# LamplightController.net
KiCad netlist of a schematic drawn in Altium Designer
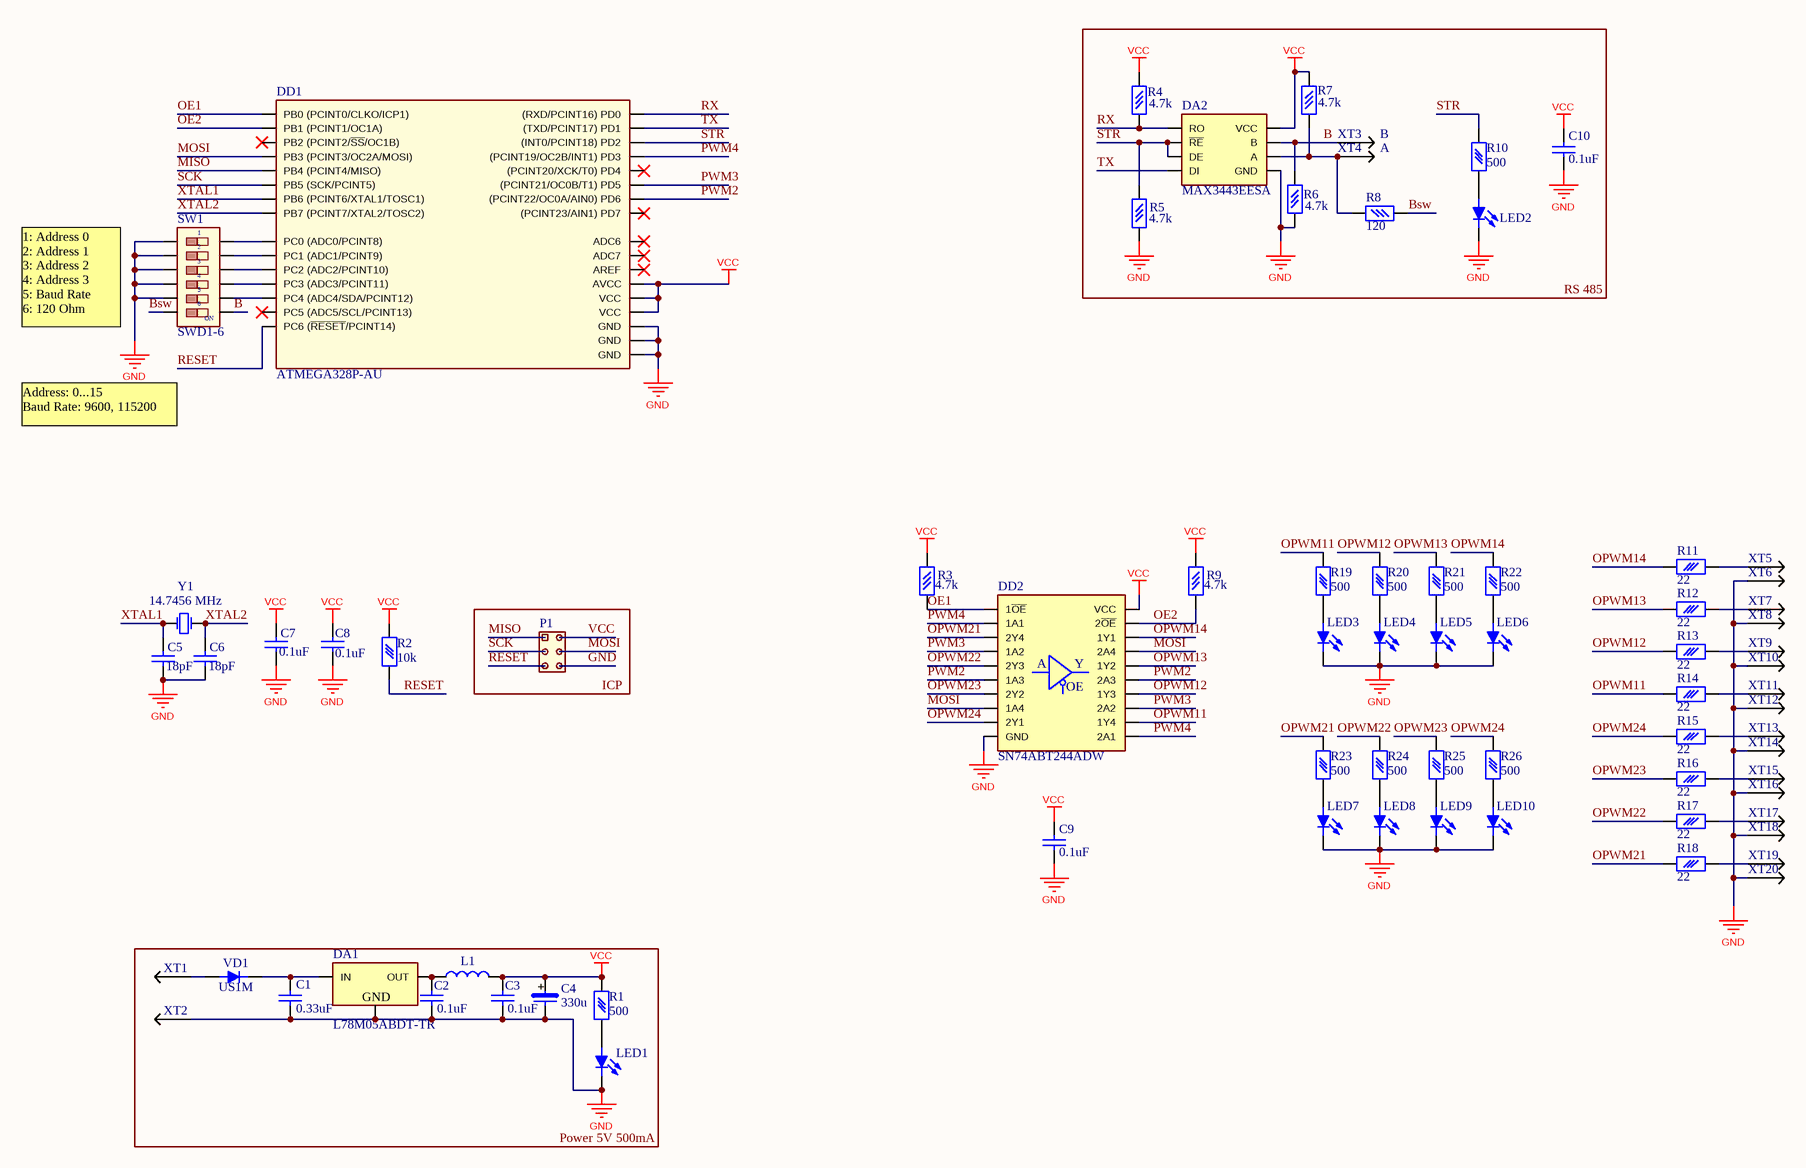
[diagram p0: LamplightController.SchDoc]

(export (version "E")
  (design (tool "Eeschema 10.0.6"))
  (components
    (comp (ref "C1")
      (value "0.33uF")
      (footprint "1206_CAP")
      (description "Конденсатор (1206)")
      (fields (field (name "Comment") "C_1206"))
      (libsource (lib "ElF_Lib") (part "C_1206"))
    )
    (comp (ref "C2")
      (value "0.1uF")
      (footprint "0603_CAP")
      (description "Конденсатор (0603)")
      (fields (field (name "Comment") "C_0603"))
      (libsource (lib "ElF_Lib") (part "C_0603"))
    )
    (comp (ref "C3")
      (value "0.1uF")
      (footprint "0603_CAP")
      (description "Конденсатор (0603)")
      (fields (field (name "Comment") "C_0603"))
      (libsource (lib "ElF_Lib") (part "C_0603"))
    )
    (comp (ref "C4")
      (value "330u")
      (footprint "case D")
      (description "Танаталовый чип конденсатор (Case D)")
      (fields (field (name "Comment") "C_caseD"))
      (libsource (lib "ElF_Lib") (part "C_caseD"))
    )
    (comp (ref "C5")
      (value "18pF")
      (footprint "0603_CAP")
      (description "Конденсатор (0603)")
      (fields (field (name "Comment") "C_0603"))
      (libsource (lib "ElF_Lib") (part "C_0603"))
    )
    (comp (ref "C6")
      (value "18pF")
      (footprint "0603_CAP")
      (description "Конденсатор (0603)")
      (fields (field (name "Comment") "C_0603"))
      (libsource (lib "ElF_Lib") (part "C_0603"))
    )
    (comp (ref "C7")
      (value "0.1uF")
      (footprint "0603_CAP")
      (description "Конденсатор (0603)")
      (fields (field (name "Comment") "C_0603"))
      (libsource (lib "ElF_Lib") (part "C_0603"))
    )
    (comp (ref "C8")
      (value "0.1uF")
      (footprint "0603_CAP")
      (description "Конденсатор (0603)")
      (fields (field (name "Comment") "C_0603"))
      (libsource (lib "ElF_Lib") (part "C_0603"))
    )
    (comp (ref "C9")
      (value "0.1uF")
      (footprint "0603_CAP")
      (description "Конденсатор (0603)")
      (fields (field (name "Comment") "C_0603"))
      (libsource (lib "ElF_Lib") (part "C_0603"))
    )
    (comp (ref "C10")
      (value "0.1uF")
      (footprint "0603_CAP")
      (description "Конденсатор (0603)")
      (fields (field (name "Comment") "C_0603"))
      (libsource (lib "ElF_Lib") (part "C_0603"))
    )
    (comp (ref "DA1")
      (value "L78M05ABDT-TR")
      (footprint "DPACK")
      (description "Precision 500 mA regulator 5V")
      (libsource (lib "ElF_Lib") (part "L78M05ABDT-TR"))
    )
    (comp (ref "DA2")
      (value "MAX3443EESA")
      (footprint "SOIC8")
      (description "5 V RS-485 Transceiver")
      (fields
        (field (name "MANUFACTURER") "Maxim Integrated Products")
        (field (name "MANUFACTURER PART NUMBER") "MAX3443EESA+")
      )
      (libsource (lib "ElF_Lib") (part "MAX3443EESA"))
    )
    (comp (ref "DD1")
      (value "ATMEGA328P-AU")
      (footprint "TQFP32")
      (description "ATMEL 8-BIT MICROCONTROLLER WITH 32KBYTES  IN-SYSTEM PROGRAMMABLE FLASH 2K RAM 20MHz")
      (libsource (lib "ElF_Lib") (part "ATMEGA328P-AU"))
    )
    (comp (ref "DD2")
      (value "SN74ABT244ADW")
      (footprint "SOIC20")
      (description "Octal Buffers/Drivers with 3-state outputs")
      (libsource (lib "ElF_Lib") (part "SN74ABT244ADW"))
    )
    (comp (ref "L1")
      (value "BLM21")
      (footprint "0805_IND")
      (description "Chip Ferrite Bead (0805 Size) BLM21PG221SH1")
      (libsource (lib "ElF_Lib") (part "BLM21"))
    )
    (comp (ref "LED1")
      (value "LED_0603")
      (footprint "0603_LED")
      (description "Светодиод 0603")
      (libsource (lib "ElF_Lib") (part "LED_0603"))
    )
    (comp (ref "LED2")
      (value "LED_0603")
      (footprint "0603_LED")
      (description "Светодиод 0603")
      (libsource (lib "ElF_Lib") (part "LED_0603"))
    )
    (comp (ref "LED3")
      (value "LED_0603")
      (footprint "0603_LED")
      (description "Светодиод 0603")
      (libsource (lib "ElF_Lib") (part "LED_0603"))
    )
    (comp (ref "LED4")
      (value "LED_0603")
      (footprint "0603_LED")
      (description "Светодиод 0603")
      (libsource (lib "ElF_Lib") (part "LED_0603"))
    )
    (comp (ref "LED5")
      (value "LED_0603")
      (footprint "0603_LED")
      (description "Светодиод 0603")
      (libsource (lib "ElF_Lib") (part "LED_0603"))
    )
    (comp (ref "LED6")
      (value "LED_0603")
      (footprint "0603_LED")
      (description "Светодиод 0603")
      (libsource (lib "ElF_Lib") (part "LED_0603"))
    )
    (comp (ref "LED7")
      (value "LED_0603")
      (footprint "0603_LED")
      (description "Светодиод 0603")
      (libsource (lib "ElF_Lib") (part "LED_0603"))
    )
    (comp (ref "LED8")
      (value "LED_0603")
      (footprint "0603_LED")
      (description "Светодиод 0603")
      (libsource (lib "ElF_Lib") (part "LED_0603"))
    )
    (comp (ref "LED9")
      (value "LED_0603")
      (footprint "0603_LED")
      (description "Светодиод 0603")
      (libsource (lib "ElF_Lib") (part "LED_0603"))
    )
    (comp (ref "LED10")
      (value "LED_0603")
      (footprint "0603_LED")
      (description "Светодиод 0603")
      (libsource (lib "ElF_Lib") (part "LED_0603"))
    )
    (comp (ref "P1") (value "BH-06M") (footprint "BH-06M") (libsource (lib "ElF_Lib") (part "BH-06M")))
    (comp (ref "R1")
      (value "500")
      (footprint "0603_RES")
      (description "Резистор 0.1 Вт (0603)")
      (fields (field (name "Comment") "R_0603"))
      (libsource (lib "") (part "R_0603_3"))
    )
    (comp (ref "R2")
      (value "10k")
      (footprint "0603_RES")
      (description "Резистор 0.1 Вт (0603)")
      (fields (field (name "Comment") "R_0603"))
      (libsource (lib "") (part "R_0603_3"))
    )
    (comp (ref "R3")
      (value "4.7k")
      (footprint "0603_RES")
      (description "Резистор 0.063 Вт (0603)")
      (fields (field (name "Comment") "R_0603"))
      (libsource (lib "") (part "R_0603_2"))
    )
    (comp (ref "R4")
      (value "4.7k")
      (footprint "0603_RES")
      (description "Резистор 0.063 Вт (0603)")
      (fields (field (name "Comment") "R_0603"))
      (libsource (lib "") (part "R_0603_2"))
    )
    (comp (ref "R5")
      (value "4.7k")
      (footprint "0603_RES")
      (description "Резистор 0.063 Вт (0603)")
      (fields (field (name "Comment") "R_0603"))
      (libsource (lib "") (part "R_0603_2"))
    )
    (comp (ref "R6")
      (value "4.7k")
      (footprint "0603_RES")
      (description "Резистор 0.063 Вт (0603)")
      (fields (field (name "Comment") "R_0603"))
      (libsource (lib "") (part "R_0603_2"))
    )
    (comp (ref "R7")
      (value "4.7k")
      (footprint "0603_RES")
      (description "Резистор 0.063 Вт (0603)")
      (fields (field (name "Comment") "R_0603"))
      (libsource (lib "") (part "R_0603_2"))
    )
    (comp (ref "R8")
      (value "120")
      (footprint "0603_RES")
      (description "Резистор 0.063 Вт (0603)")
      (fields (field (name "Comment") "R_0603"))
      (libsource (lib "") (part "R_0603_4"))
    )
    (comp (ref "R9")
      (value "4.7k")
      (footprint "0603_RES")
      (description "Резистор 0.063 Вт (0603)")
      (fields (field (name "Comment") "R_0603"))
      (libsource (lib "") (part "R_0603_2"))
    )
    (comp (ref "R10")
      (value "500")
      (footprint "0603_RES")
      (description "Резистор 0.1 Вт (0603)")
      (fields (field (name "Comment") "R_0603"))
      (libsource (lib "") (part "R_0603_3"))
    )
    (comp (ref "R11")
      (value "22")
      (footprint "0603_RES")
      (description "Резистор 0.1 Вт (0603)")
      (fields (field (name "Comment") "R_0603"))
      (libsource (lib "ElF_Lib") (part "R_0603"))
    )
    (comp (ref "R12")
      (value "22")
      (footprint "0603_RES")
      (description "Резистор 0.1 Вт (0603)")
      (fields (field (name "Comment") "R_0603"))
      (libsource (lib "ElF_Lib") (part "R_0603"))
    )
    (comp (ref "R13")
      (value "22")
      (footprint "0603_RES")
      (description "Резистор 0.1 Вт (0603)")
      (fields (field (name "Comment") "R_0603"))
      (libsource (lib "ElF_Lib") (part "R_0603"))
    )
    (comp (ref "R14")
      (value "22")
      (footprint "0603_RES")
      (description "Резистор 0.1 Вт (0603)")
      (fields (field (name "Comment") "R_0603"))
      (libsource (lib "ElF_Lib") (part "R_0603"))
    )
    (comp (ref "R15")
      (value "22")
      (footprint "0603_RES")
      (description "Резистор 0.1 Вт (0603)")
      (fields (field (name "Comment") "R_0603"))
      (libsource (lib "ElF_Lib") (part "R_0603"))
    )
    (comp (ref "R16")
      (value "22")
      (footprint "0603_RES")
      (description "Резистор 0.1 Вт (0603)")
      (fields (field (name "Comment") "R_0603"))
      (libsource (lib "ElF_Lib") (part "R_0603"))
    )
    (comp (ref "R17")
      (value "22")
      (footprint "0603_RES")
      (description "Резистор 0.1 Вт (0603)")
      (fields (field (name "Comment") "R_0603"))
      (libsource (lib "ElF_Lib") (part "R_0603"))
    )
    (comp (ref "R18")
      (value "22")
      (footprint "0603_RES")
      (description "Резистор 0.1 Вт (0603)")
      (fields (field (name "Comment") "R_0603"))
      (libsource (lib "ElF_Lib") (part "R_0603"))
    )
    (comp (ref "R19")
      (value "500")
      (footprint "0603_RES")
      (description "Резистор 0.1 Вт (0603)")
      (fields (field (name "Comment") "R_0603"))
      (libsource (lib "") (part "R_0603_1"))
    )
    (comp (ref "R20")
      (value "500")
      (footprint "0603_RES")
      (description "Резистор 0.1 Вт (0603)")
      (fields (field (name "Comment") "R_0603"))
      (libsource (lib "") (part "R_0603_1"))
    )
    (comp (ref "R21")
      (value "500")
      (footprint "0603_RES")
      (description "Резистор 0.1 Вт (0603)")
      (fields (field (name "Comment") "R_0603"))
      (libsource (lib "") (part "R_0603_1"))
    )
    (comp (ref "R22")
      (value "500")
      (footprint "0603_RES")
      (description "Резистор 0.1 Вт (0603)")
      (fields (field (name "Comment") "R_0603"))
      (libsource (lib "") (part "R_0603_1"))
    )
    (comp (ref "R23")
      (value "500")
      (footprint "0603_RES")
      (description "Резистор 0.1 Вт (0603)")
      (fields (field (name "Comment") "R_0603"))
      (libsource (lib "") (part "R_0603_1"))
    )
    (comp (ref "R24")
      (value "500")
      (footprint "0603_RES")
      (description "Резистор 0.1 Вт (0603)")
      (fields (field (name "Comment") "R_0603"))
      (libsource (lib "") (part "R_0603_1"))
    )
    (comp (ref "R25")
      (value "500")
      (footprint "0603_RES")
      (description "Резистор 0.1 Вт (0603)")
      (fields (field (name "Comment") "R_0603"))
      (libsource (lib "") (part "R_0603_1"))
    )
    (comp (ref "R26")
      (value "500")
      (footprint "0603_RES")
      (description "Резистор 0.1 Вт (0603)")
      (fields (field (name "Comment") "R_0603"))
      (libsource (lib "") (part "R_0603_1"))
    )
    (comp (ref "SW1")
      (value "SWD1-6")
      (footprint "DIP_SW 12")
      (description "DIP-переключатель 2-х полож. 6 кн. 2.54mm")
      (libsource (lib "ElF_Lib") (part "SWD1-6"))
    )
    (comp (ref "VD1")
      (value "US1M")
      (footprint "SMA")
      (description "Диод 1А до 1000V")
      (fields
        (field (name "MANUFACTURER") "Diodes Inc")
        (field (name "MANUFACTURER PART NUMBER") "US1J-13-F")
      )
      (libsource (lib "ElF_Lib") (part "US1M"))
    )
    (comp (ref "XT1")
      (value "235-101")
      (footprint "wago235-101")
      (libsource (lib "ElF_Lib") (part "wago235-101"))
    )
    (comp (ref "XT2")
      (value "235-101")
      (footprint "wago235-101")
      (libsource (lib "ElF_Lib") (part "wago235-101"))
    )
    (comp (ref "XT3")
      (value "235-101")
      (footprint "wago235-101")
      (libsource (lib "ElF_Lib") (part "wago235-101"))
    )
    (comp (ref "XT4")
      (value "235-101")
      (footprint "wago235-101")
      (libsource (lib "ElF_Lib") (part "wago235-101"))
    )
    (comp (ref "XT5")
      (value "235-101")
      (footprint "wago235-101")
      (libsource (lib "ElF_Lib") (part "wago235-101"))
    )
    (comp (ref "XT6")
      (value "235-101")
      (footprint "wago235-101")
      (libsource (lib "ElF_Lib") (part "wago235-101"))
    )
    (comp (ref "XT7")
      (value "235-101")
      (footprint "wago235-101")
      (libsource (lib "ElF_Lib") (part "wago235-101"))
    )
    (comp (ref "XT8")
      (value "235-101")
      (footprint "wago235-101")
      (libsource (lib "ElF_Lib") (part "wago235-101"))
    )
    (comp (ref "XT9")
      (value "235-101")
      (footprint "wago235-101")
      (libsource (lib "ElF_Lib") (part "wago235-101"))
    )
    (comp (ref "XT10")
      (value "235-101")
      (footprint "wago235-101")
      (libsource (lib "ElF_Lib") (part "wago235-101"))
    )
    (comp (ref "XT11")
      (value "235-101")
      (footprint "wago235-101")
      (libsource (lib "ElF_Lib") (part "wago235-101"))
    )
    (comp (ref "XT12")
      (value "235-101")
      (footprint "wago235-101")
      (libsource (lib "ElF_Lib") (part "wago235-101"))
    )
    (comp (ref "XT13")
      (value "235-101")
      (footprint "wago235-101")
      (libsource (lib "ElF_Lib") (part "wago235-101"))
    )
    (comp (ref "XT14")
      (value "235-101")
      (footprint "wago235-101")
      (libsource (lib "ElF_Lib") (part "wago235-101"))
    )
    (comp (ref "XT15")
      (value "235-101")
      (footprint "wago235-101")
      (libsource (lib "ElF_Lib") (part "wago235-101"))
    )
    (comp (ref "XT16")
      (value "235-101")
      (footprint "wago235-101")
      (libsource (lib "ElF_Lib") (part "wago235-101"))
    )
    (comp (ref "XT17")
      (value "235-101")
      (footprint "wago235-101")
      (libsource (lib "ElF_Lib") (part "wago235-101"))
    )
    (comp (ref "XT18")
      (value "235-101")
      (footprint "wago235-101")
      (libsource (lib "ElF_Lib") (part "wago235-101"))
    )
    (comp (ref "XT19")
      (value "235-101")
      (footprint "wago235-101")
      (libsource (lib "ElF_Lib") (part "wago235-101"))
    )
    (comp (ref "XT20")
      (value "235-101")
      (footprint "wago235-101")
      (libsource (lib "ElF_Lib") (part "wago235-101"))
    )
    (comp (ref "Y1")
      (value "14.7456 MHz")
      (footprint "HC49S")
      (description "Кварцевый резонатор (HC49S)")
      (fields (field (name "Comment") "HC49S"))
      (libsource (lib "ElF_Lib") (part "Quartz_HC49S"))
    )
  )
  (nets
    (net (code "1") (name "/B") (class "Default")
      (node (ref "DA2") (pin "7") (pinfunction "B_7") (pintype "passive"))
      (node (ref "R6") (pin "2") (pinfunction "2_2") (pintype "passive"))
      (node (ref "SW1") (pin "7") (pinfunction "7_7") (pintype "passive"))
      (node (ref "XT3") (pin "1") (pinfunction "1_1") (pintype "power_in"))
    )
    (net (code "2") (name "/Bsw") (class "Default")
      (node (ref "R8") (pin "2") (pinfunction "2_2") (pintype "passive"))
      (node (ref "SW1") (pin "6") (pinfunction "6_6") (pintype "passive"))
    )
    (net (code "3") (name "/MISO") (class "Default")
      (node (ref "DD1") (pin "16") (pinfunction "PB4_(PCINT4/MISO)_16") (pintype "passive"))
      (node (ref "P1") (pin "1") (pinfunction "1_1") (pintype "power_in"))
    )
    (net (code "4") (name "/MOSI") (class "Default")
      (node (ref "DD1") (pin "15") (pinfunction "PB3_(PCINT3/OC2A/MOSI)_15") (pintype "passive"))
      (node (ref "DD2") (pin "17") (pinfunction "2A4_17") (pintype "passive"))
      (node (ref "DD2") (pin "8") (pinfunction "1A4_8") (pintype "passive"))
      (node (ref "P1") (pin "4") (pinfunction "4_4") (pintype "passive"))
    )
    (net (code "5") (name "/OE1") (class "Default")
      (node (ref "DD1") (pin "12") (pinfunction "PB0_(PCINT0/CLKO/ICP1)_12") (pintype "passive"))
      (node (ref "DD2") (pin "1") (pinfunction "1~{OE}_1") (pintype "passive"))
      (node (ref "R3") (pin "1") (pinfunction "1_1") (pintype "passive"))
    )
    (net (code "6") (name "/OE2") (class "Default")
      (node (ref "DD1") (pin "13") (pinfunction "PB1_(PCINT1/OC1A)_13") (pintype "passive"))
      (node (ref "DD2") (pin "19") (pinfunction "2~{OE}_19") (pintype "passive"))
      (node (ref "R9") (pin "1") (pinfunction "1_1") (pintype "passive"))
    )
    (net (code "7") (name "/OPWM11") (class "Default")
      (node (ref "DD2") (pin "12") (pinfunction "1Y4_12") (pintype "passive"))
      (node (ref "R14") (pin "2") (pinfunction "2_2") (pintype "passive"))
      (node (ref "R19") (pin "1") (pinfunction "1_1") (pintype "passive"))
    )
    (net (code "8") (name "/OPWM12") (class "Default")
      (node (ref "DD2") (pin "14") (pinfunction "1Y3_14") (pintype "passive"))
      (node (ref "R13") (pin "2") (pinfunction "2_2") (pintype "passive"))
      (node (ref "R20") (pin "1") (pinfunction "1_1") (pintype "passive"))
    )
    (net (code "9") (name "/OPWM13") (class "Default")
      (node (ref "DD2") (pin "16") (pinfunction "1Y2_16") (pintype "passive"))
      (node (ref "R12") (pin "2") (pinfunction "2_2") (pintype "passive"))
      (node (ref "R21") (pin "1") (pinfunction "1_1") (pintype "passive"))
    )
    (net (code "10") (name "/OPWM14") (class "Default")
      (node (ref "DD2") (pin "18") (pinfunction "1Y1_18") (pintype "passive"))
      (node (ref "R11") (pin "2") (pinfunction "2_2") (pintype "passive"))
      (node (ref "R22") (pin "1") (pinfunction "1_1") (pintype "passive"))
    )
    (net (code "11") (name "/OPWM21") (class "Default")
      (node (ref "DD2") (pin "3") (pinfunction "2Y4_3") (pintype "passive"))
      (node (ref "R18") (pin "2") (pinfunction "2_2") (pintype "passive"))
      (node (ref "R23") (pin "1") (pinfunction "1_1") (pintype "passive"))
    )
    (net (code "12") (name "/OPWM22") (class "Default")
      (node (ref "DD2") (pin "5") (pinfunction "2Y3_5") (pintype "passive"))
      (node (ref "R17") (pin "2") (pinfunction "2_2") (pintype "passive"))
      (node (ref "R24") (pin "1") (pinfunction "1_1") (pintype "passive"))
    )
    (net (code "13") (name "/OPWM23") (class "Default")
      (node (ref "DD2") (pin "7") (pinfunction "2Y2_7") (pintype "passive"))
      (node (ref "R16") (pin "2") (pinfunction "2_2") (pintype "passive"))
      (node (ref "R25") (pin "1") (pinfunction "1_1") (pintype "passive"))
    )
    (net (code "14") (name "/OPWM24") (class "Default")
      (node (ref "DD2") (pin "9") (pinfunction "2Y1_9") (pintype "passive"))
      (node (ref "R15") (pin "2") (pinfunction "2_2") (pintype "passive"))
      (node (ref "R26") (pin "1") (pinfunction "1_1") (pintype "passive"))
    )
    (net (code "15") (name "/PWM2") (class "Default")
      (node (ref "DD1") (pin "10") (pinfunction "(PCINT22/OC0A/AIN0)_PD6_10") (pintype "passive"))
      (node (ref "DD2") (pin "15") (pinfunction "2A3_15") (pintype "passive"))
      (node (ref "DD2") (pin "6") (pinfunction "1A3_6") (pintype "passive"))
    )
    (net (code "16") (name "/PWM3") (class "Default")
      (node (ref "DD1") (pin "9") (pinfunction "(PCINT21/OC0B/T1)_PD5_9") (pintype "passive"))
      (node (ref "DD2") (pin "13") (pinfunction "2A2_13") (pintype "passive"))
      (node (ref "DD2") (pin "4") (pinfunction "1A2_4") (pintype "passive"))
    )
    (net (code "17") (name "/PWM4") (class "Default")
      (node (ref "DD1") (pin "1") (pinfunction "(PCINT19/OC2B/INT1)_PD3_1") (pintype "passive"))
      (node (ref "DD2") (pin "11") (pinfunction "2A1_11") (pintype "passive"))
      (node (ref "DD2") (pin "2") (pinfunction "1A1_2") (pintype "passive"))
    )
    (net (code "18") (name "/RESET") (class "Default")
      (node (ref "DD1") (pin "29") (pinfunction "PC6_(~{RESET}/PCINT14)_29") (pintype "passive"))
      (node (ref "P1") (pin "5") (pinfunction "5_5") (pintype "passive"))
      (node (ref "R2") (pin "1") (pinfunction "1_1") (pintype "passive"))
    )
    (net (code "19") (name "/RX") (class "Default")
      (node (ref "DA2") (pin "1") (pinfunction "RO_1") (pintype "passive"))
      (node (ref "DD1") (pin "30") (pinfunction "(RXD/PCINT16)_PD0_30") (pintype "passive"))
      (node (ref "R4") (pin "1") (pinfunction "1_1") (pintype "passive"))
    )
    (net (code "20") (name "/SCK") (class "Default")
      (node (ref "DD1") (pin "17") (pinfunction "PB5_(SCK/PCINT5)_17") (pintype "passive"))
      (node (ref "P1") (pin "3") (pinfunction "3_3") (pintype "passive"))
    )
    (net (code "21") (name "/STR") (class "Default")
      (node (ref "DA2") (pin "2") (pinfunction "~{RE}_2") (pintype "passive"))
      (node (ref "DA2") (pin "3") (pinfunction "DE_3") (pintype "passive"))
      (node (ref "DD1") (pin "32") (pinfunction "(INT0/PCINT18)_PD2_32") (pintype "passive"))
      (node (ref "R10") (pin "2") (pinfunction "2_2") (pintype "passive"))
      (node (ref "R5") (pin "2") (pinfunction "2_2") (pintype "passive"))
    )
    (net (code "22") (name "/TX") (class "Default")
      (node (ref "DA2") (pin "4") (pinfunction "DI_4") (pintype "passive"))
      (node (ref "DD1") (pin "31") (pinfunction "(TXD/PCINT17)_PD1_31") (pintype "passive"))
    )
    (net (code "23") (name "/XTAL1") (class "Default")
      (node (ref "C5") (pin "2") (pinfunction "2_2") (pintype "passive"))
      (node (ref "DD1") (pin "7") (pinfunction "PB6_(PCINT6/XTAL1/TOSC1)_7") (pintype "passive"))
      (node (ref "Y1") (pin "2") (pinfunction "OSC2_2") (pintype "passive"))
    )
    (net (code "24") (name "/XTAL2") (class "Default")
      (node (ref "C6") (pin "2") (pinfunction "2_2") (pintype "passive"))
      (node (ref "DD1") (pin "8") (pinfunction "PB7_(PCINT7/XTAL2/TOSC2)_8") (pintype "passive"))
      (node (ref "Y1") (pin "1") (pinfunction "OSC1_1") (pintype "passive"))
    )
    (net (code "25") (name "GND") (class "Default")
      (node (ref "C1") (pin "1") (pinfunction "1_1") (pintype "passive"))
      (node (ref "C10") (pin "2") (pinfunction "2_2") (pintype "passive"))
      (node (ref "C2") (pin "1") (pinfunction "1_1") (pintype "passive"))
      (node (ref "C3") (pin "1") (pinfunction "1_1") (pintype "passive"))
      (node (ref "C4") (pin "2") (pinfunction "-_2") (pintype "passive"))
      (node (ref "C5") (pin "1") (pinfunction "1_1") (pintype "passive"))
      (node (ref "C6") (pin "1") (pinfunction "1_1") (pintype "passive"))
      (node (ref "C7") (pin "1") (pinfunction "1_1") (pintype "passive"))
      (node (ref "C8") (pin "1") (pinfunction "1_1") (pintype "passive"))
      (node (ref "C9") (pin "2") (pinfunction "2_2") (pintype "passive"))
      (node (ref "DA1") (pin "3") (pinfunction "GND_3") (pintype "passive"))
      (node (ref "DA2") (pin "5") (pinfunction "GND_5") (pintype "passive"))
      (node (ref "DD1") (pin "21") (pinfunction "GND_21") (pintype "passive"))
      (node (ref "DD1") (pin "3") (pinfunction "GND_3") (pintype "passive"))
      (node (ref "DD1") (pin "5") (pinfunction "GND_5") (pintype "passive"))
      (node (ref "DD2") (pin "10") (pinfunction "GND_10") (pintype "passive"))
      (node (ref "LED1") (pin "2") (pinfunction "C_2") (pintype "passive"))
      (node (ref "LED10") (pin "2") (pinfunction "C_2") (pintype "passive"))
      (node (ref "LED2") (pin "2") (pinfunction "C_2") (pintype "passive"))
      (node (ref "LED3") (pin "2") (pinfunction "C_2") (pintype "passive"))
      (node (ref "LED4") (pin "2") (pinfunction "C_2") (pintype "passive"))
      (node (ref "LED5") (pin "2") (pinfunction "C_2") (pintype "passive"))
      (node (ref "LED6") (pin "2") (pinfunction "C_2") (pintype "passive"))
      (node (ref "LED7") (pin "2") (pinfunction "C_2") (pintype "passive"))
      (node (ref "LED8") (pin "2") (pinfunction "C_2") (pintype "passive"))
      (node (ref "LED9") (pin "2") (pinfunction "C_2") (pintype "passive"))
      (node (ref "P1") (pin "6") (pinfunction "6_6") (pintype "passive"))
      (node (ref "R5") (pin "1") (pinfunction "1_1") (pintype "passive"))
      (node (ref "R6") (pin "1") (pinfunction "1_1") (pintype "passive"))
      (node (ref "SW1") (pin "1") (pinfunction "1_1") (pintype "passive"))
      (node (ref "SW1") (pin "2") (pinfunction "2_2") (pintype "passive"))
      (node (ref "SW1") (pin "3") (pinfunction "3_3") (pintype "passive"))
      (node (ref "SW1") (pin "4") (pinfunction "4_4") (pintype "passive"))
      (node (ref "SW1") (pin "5") (pinfunction "5_5") (pintype "passive"))
      (node (ref "XT10") (pin "1") (pinfunction "1_1") (pintype "power_in"))
      (node (ref "XT12") (pin "1") (pinfunction "1_1") (pintype "power_in"))
      (node (ref "XT14") (pin "1") (pinfunction "1_1") (pintype "power_in"))
      (node (ref "XT16") (pin "1") (pinfunction "1_1") (pintype "power_in"))
      (node (ref "XT18") (pin "1") (pinfunction "1_1") (pintype "power_in"))
      (node (ref "XT2") (pin "1") (pinfunction "1_1") (pintype "power_in"))
      (node (ref "XT20") (pin "1") (pinfunction "1_1") (pintype "power_in"))
      (node (ref "XT6") (pin "1") (pinfunction "1_1") (pintype "power_in"))
      (node (ref "XT8") (pin "1") (pinfunction "1_1") (pintype "power_in"))
    )
    (net (code "26") (name "Net-(DA1-IN)") (class "Default")
      (node (ref "C1") (pin "2") (pinfunction "2_2") (pintype "passive"))
      (node (ref "DA1") (pin "1") (pinfunction "IN_1") (pintype "passive"))
      (node (ref "VD1") (pin "2") (pinfunction "C_2") (pintype "passive"))
    )
    (net (code "27") (name "Net-(DA1-OUT)") (class "Default")
      (node (ref "C2") (pin "2") (pinfunction "2_2") (pintype "passive"))
      (node (ref "DA1") (pin "2") (pinfunction "OUT_2") (pintype "passive"))
      (node (ref "L1") (pin "1") (pinfunction "1_1") (pintype "passive"))
    )
    (net (code "28") (name "Net-(DA2-A)") (class "Default")
      (node (ref "DA2") (pin "6") (pinfunction "A_6") (pintype "passive"))
      (node (ref "R7") (pin "1") (pinfunction "1_1") (pintype "passive"))
      (node (ref "R8") (pin "1") (pinfunction "1_1") (pintype "passive"))
      (node (ref "XT4") (pin "1") (pinfunction "1_1") (pintype "power_in"))
    )
    (net (code "29") (name "Net-(DD1-PC0_(ADC0{slash}PCINT8))") (class "Default")
      (node (ref "DD1") (pin "23") (pinfunction "PC0_(ADC0/PCINT8)_23") (pintype "passive"))
      (node (ref "SW1") (pin "12") (pinfunction "12_12") (pintype "passive"))
    )
    (net (code "30") (name "Net-(DD1-PC1_(ADC1{slash}PCINT9))") (class "Default")
      (node (ref "DD1") (pin "24") (pinfunction "PC1_(ADC1/PCINT9)_24") (pintype "passive"))
      (node (ref "SW1") (pin "11") (pinfunction "11_11") (pintype "passive"))
    )
    (net (code "31") (name "Net-(DD1-PC2_(ADC2{slash}PCINT10))") (class "Default")
      (node (ref "DD1") (pin "25") (pinfunction "PC2_(ADC2/PCINT10)_25") (pintype "passive"))
      (node (ref "SW1") (pin "10") (pinfunction "10_10") (pintype "passive"))
    )
    (net (code "32") (name "Net-(DD1-PC3_(ADC3{slash}PCINT11))") (class "Default")
      (node (ref "DD1") (pin "26") (pinfunction "PC3_(ADC3/PCINT11)_26") (pintype "passive"))
      (node (ref "SW1") (pin "9") (pinfunction "9_9") (pintype "passive"))
    )
    (net (code "33") (name "Net-(DD1-PC4_(ADC4{slash}SDA{slash}PCINT12))") (class "Default")
      (node (ref "DD1") (pin "27") (pinfunction "PC4_(ADC4/SDA/PCINT12)_27") (pintype "passive"))
      (node (ref "SW1") (pin "8") (pinfunction "8_8") (pintype "passive"))
    )
    (net (code "34") (name "Net-(LED1-A)") (class "Default")
      (node (ref "LED1") (pin "1") (pinfunction "A_1") (pintype "passive"))
      (node (ref "R1") (pin "1") (pinfunction "1_1") (pintype "passive"))
    )
    (net (code "35") (name "Net-(LED2-A)") (class "Default")
      (node (ref "LED2") (pin "1") (pinfunction "A_1") (pintype "passive"))
      (node (ref "R10") (pin "1") (pinfunction "1_1") (pintype "passive"))
    )
    (net (code "36") (name "Net-(LED3-A)") (class "Default")
      (node (ref "LED3") (pin "1") (pinfunction "A_1") (pintype "passive"))
      (node (ref "R19") (pin "2") (pinfunction "2_2") (pintype "passive"))
    )
    (net (code "37") (name "Net-(LED4-A)") (class "Default")
      (node (ref "LED4") (pin "1") (pinfunction "A_1") (pintype "passive"))
      (node (ref "R20") (pin "2") (pinfunction "2_2") (pintype "passive"))
    )
    (net (code "38") (name "Net-(LED5-A)") (class "Default")
      (node (ref "LED5") (pin "1") (pinfunction "A_1") (pintype "passive"))
      (node (ref "R21") (pin "2") (pinfunction "2_2") (pintype "passive"))
    )
    (net (code "39") (name "Net-(LED6-A)") (class "Default")
      (node (ref "LED6") (pin "1") (pinfunction "A_1") (pintype "passive"))
      (node (ref "R22") (pin "2") (pinfunction "2_2") (pintype "passive"))
    )
    (net (code "40") (name "Net-(LED7-A)") (class "Default")
      (node (ref "LED7") (pin "1") (pinfunction "A_1") (pintype "passive"))
      (node (ref "R23") (pin "2") (pinfunction "2_2") (pintype "passive"))
    )
    (net (code "41") (name "Net-(LED8-A)") (class "Default")
      (node (ref "LED8") (pin "1") (pinfunction "A_1") (pintype "passive"))
      (node (ref "R24") (pin "2") (pinfunction "2_2") (pintype "passive"))
    )
    (net (code "42") (name "Net-(LED9-A)") (class "Default")
      (node (ref "LED9") (pin "1") (pinfunction "A_1") (pintype "passive"))
      (node (ref "R25") (pin "2") (pinfunction "2_2") (pintype "passive"))
    )
    (net (code "43") (name "Net-(LED10-A)") (class "Default")
      (node (ref "LED10") (pin "1") (pinfunction "A_1") (pintype "passive"))
      (node (ref "R26") (pin "2") (pinfunction "2_2") (pintype "passive"))
    )
    (net (code "44") (name "Net-(R11-Pad1)") (class "Default")
      (node (ref "R11") (pin "1") (pinfunction "1_1") (pintype "passive"))
      (node (ref "XT5") (pin "1") (pinfunction "1_1") (pintype "power_in"))
    )
    (net (code "45") (name "Net-(R12-Pad1)") (class "Default")
      (node (ref "R12") (pin "1") (pinfunction "1_1") (pintype "passive"))
      (node (ref "XT7") (pin "1") (pinfunction "1_1") (pintype "power_in"))
    )
    (net (code "46") (name "Net-(R13-Pad1)") (class "Default")
      (node (ref "R13") (pin "1") (pinfunction "1_1") (pintype "passive"))
      (node (ref "XT9") (pin "1") (pinfunction "1_1") (pintype "power_in"))
    )
    (net (code "47") (name "Net-(R14-Pad1)") (class "Default")
      (node (ref "R14") (pin "1") (pinfunction "1_1") (pintype "passive"))
      (node (ref "XT11") (pin "1") (pinfunction "1_1") (pintype "power_in"))
    )
    (net (code "48") (name "Net-(R15-Pad1)") (class "Default")
      (node (ref "R15") (pin "1") (pinfunction "1_1") (pintype "passive"))
      (node (ref "XT13") (pin "1") (pinfunction "1_1") (pintype "power_in"))
    )
    (net (code "49") (name "Net-(R16-Pad1)") (class "Default")
      (node (ref "R16") (pin "1") (pinfunction "1_1") (pintype "passive"))
      (node (ref "XT15") (pin "1") (pinfunction "1_1") (pintype "power_in"))
    )
    (net (code "50") (name "Net-(R17-Pad1)") (class "Default")
      (node (ref "R17") (pin "1") (pinfunction "1_1") (pintype "passive"))
      (node (ref "XT17") (pin "1") (pinfunction "1_1") (pintype "power_in"))
    )
    (net (code "51") (name "Net-(R18-Pad1)") (class "Default")
      (node (ref "R18") (pin "1") (pinfunction "1_1") (pintype "passive"))
      (node (ref "XT19") (pin "1") (pinfunction "1_1") (pintype "power_in"))
    )
    (net (code "52") (name "Net-(VD1-A)") (class "Default")
      (node (ref "VD1") (pin "1") (pinfunction "A_1") (pintype "passive"))
      (node (ref "XT1") (pin "1") (pinfunction "1_1") (pintype "power_in"))
    )
    (net (code "53") (name "VCC") (class "Default")
      (node (ref "C10") (pin "1") (pinfunction "1_1") (pintype "passive"))
      (node (ref "C3") (pin "2") (pinfunction "2_2") (pintype "passive"))
      (node (ref "C4") (pin "1") (pinfunction "+_1") (pintype "passive"))
      (node (ref "C7") (pin "2") (pinfunction "2_2") (pintype "passive"))
      (node (ref "C8") (pin "2") (pinfunction "2_2") (pintype "passive"))
      (node (ref "C9") (pin "1") (pinfunction "1_1") (pintype "passive"))
      (node (ref "DA2") (pin "8") (pinfunction "VCC_8") (pintype "passive"))
      (node (ref "DD1") (pin "18") (pinfunction "AVCC_18") (pintype "passive"))
      (node (ref "DD1") (pin "4") (pinfunction "VCC_4") (pintype "passive"))
      (node (ref "DD1") (pin "6") (pinfunction "VCC_6") (pintype "passive"))
      (node (ref "DD2") (pin "20") (pinfunction "VCC_20") (pintype "passive"))
      (node (ref "L1") (pin "2") (pinfunction "2_2") (pintype "passive"))
      (node (ref "P1") (pin "2") (pinfunction "2_2") (pintype "passive"))
      (node (ref "R1") (pin "2") (pinfunction "2_2") (pintype "passive"))
      (node (ref "R2") (pin "2") (pinfunction "2_2") (pintype "passive"))
      (node (ref "R3") (pin "2") (pinfunction "2_2") (pintype "passive"))
      (node (ref "R4") (pin "2") (pinfunction "2_2") (pintype "passive"))
      (node (ref "R7") (pin "2") (pinfunction "2_2") (pintype "passive"))
      (node (ref "R9") (pin "2") (pinfunction "2_2") (pintype "passive"))
    )
    (net (code "54") (name "unconnected-(DD1-(PCINT20{slash}XCK{slash}T0)_PD4-Pad2)") (class "Default")
      (node (ref "DD1") (pin "2") (pinfunction "(PCINT20/XCK/T0)_PD4_2") (pintype "passive+no_connect"))
    )
    (net (code "55") (name "unconnected-(DD1-(PCINT23{slash}AIN1)_PD7-Pad11)") (class "Default")
      (node (ref "DD1") (pin "11") (pinfunction "(PCINT23/AIN1)_PD7_11") (pintype "passive+no_connect"))
    )
    (net (code "56") (name "unconnected-(DD1-ADC6-Pad19)") (class "Default")
      (node (ref "DD1") (pin "19") (pinfunction "ADC6_19") (pintype "passive+no_connect"))
    )
    (net (code "57") (name "unconnected-(DD1-ADC7-Pad22)") (class "Default")
      (node (ref "DD1") (pin "22") (pinfunction "ADC7_22") (pintype "passive+no_connect"))
    )
    (net (code "58") (name "unconnected-(DD1-AREF-Pad20)") (class "Default")
      (node (ref "DD1") (pin "20") (pinfunction "AREF_20") (pintype "passive+no_connect"))
    )
    (net (code "59") (name "unconnected-(DD1-PB2_(PCINT2{slash}~{SS}{slash}OC1B)-Pad14)") (class "Default")
      (node (ref "DD1") (pin "14") (pinfunction "PB2_(PCINT2/~{SS}/OC1B)_14") (pintype "passive+no_connect"))
    )
    (net (code "60") (name "unconnected-(DD1-PC5_(ADC5{slash}SCL{slash}PCINT13)-Pad28)") (class "Default")
      (node (ref "DD1") (pin "28") (pinfunction "PC5_(ADC5/SCL/PCINT13)_28") (pintype "passive+no_connect"))
    )
  )
)
